# 00_dynaRoACH_MotorDriver_1_Chan.net
KiCad netlist of a schematic drawn in EAGLE
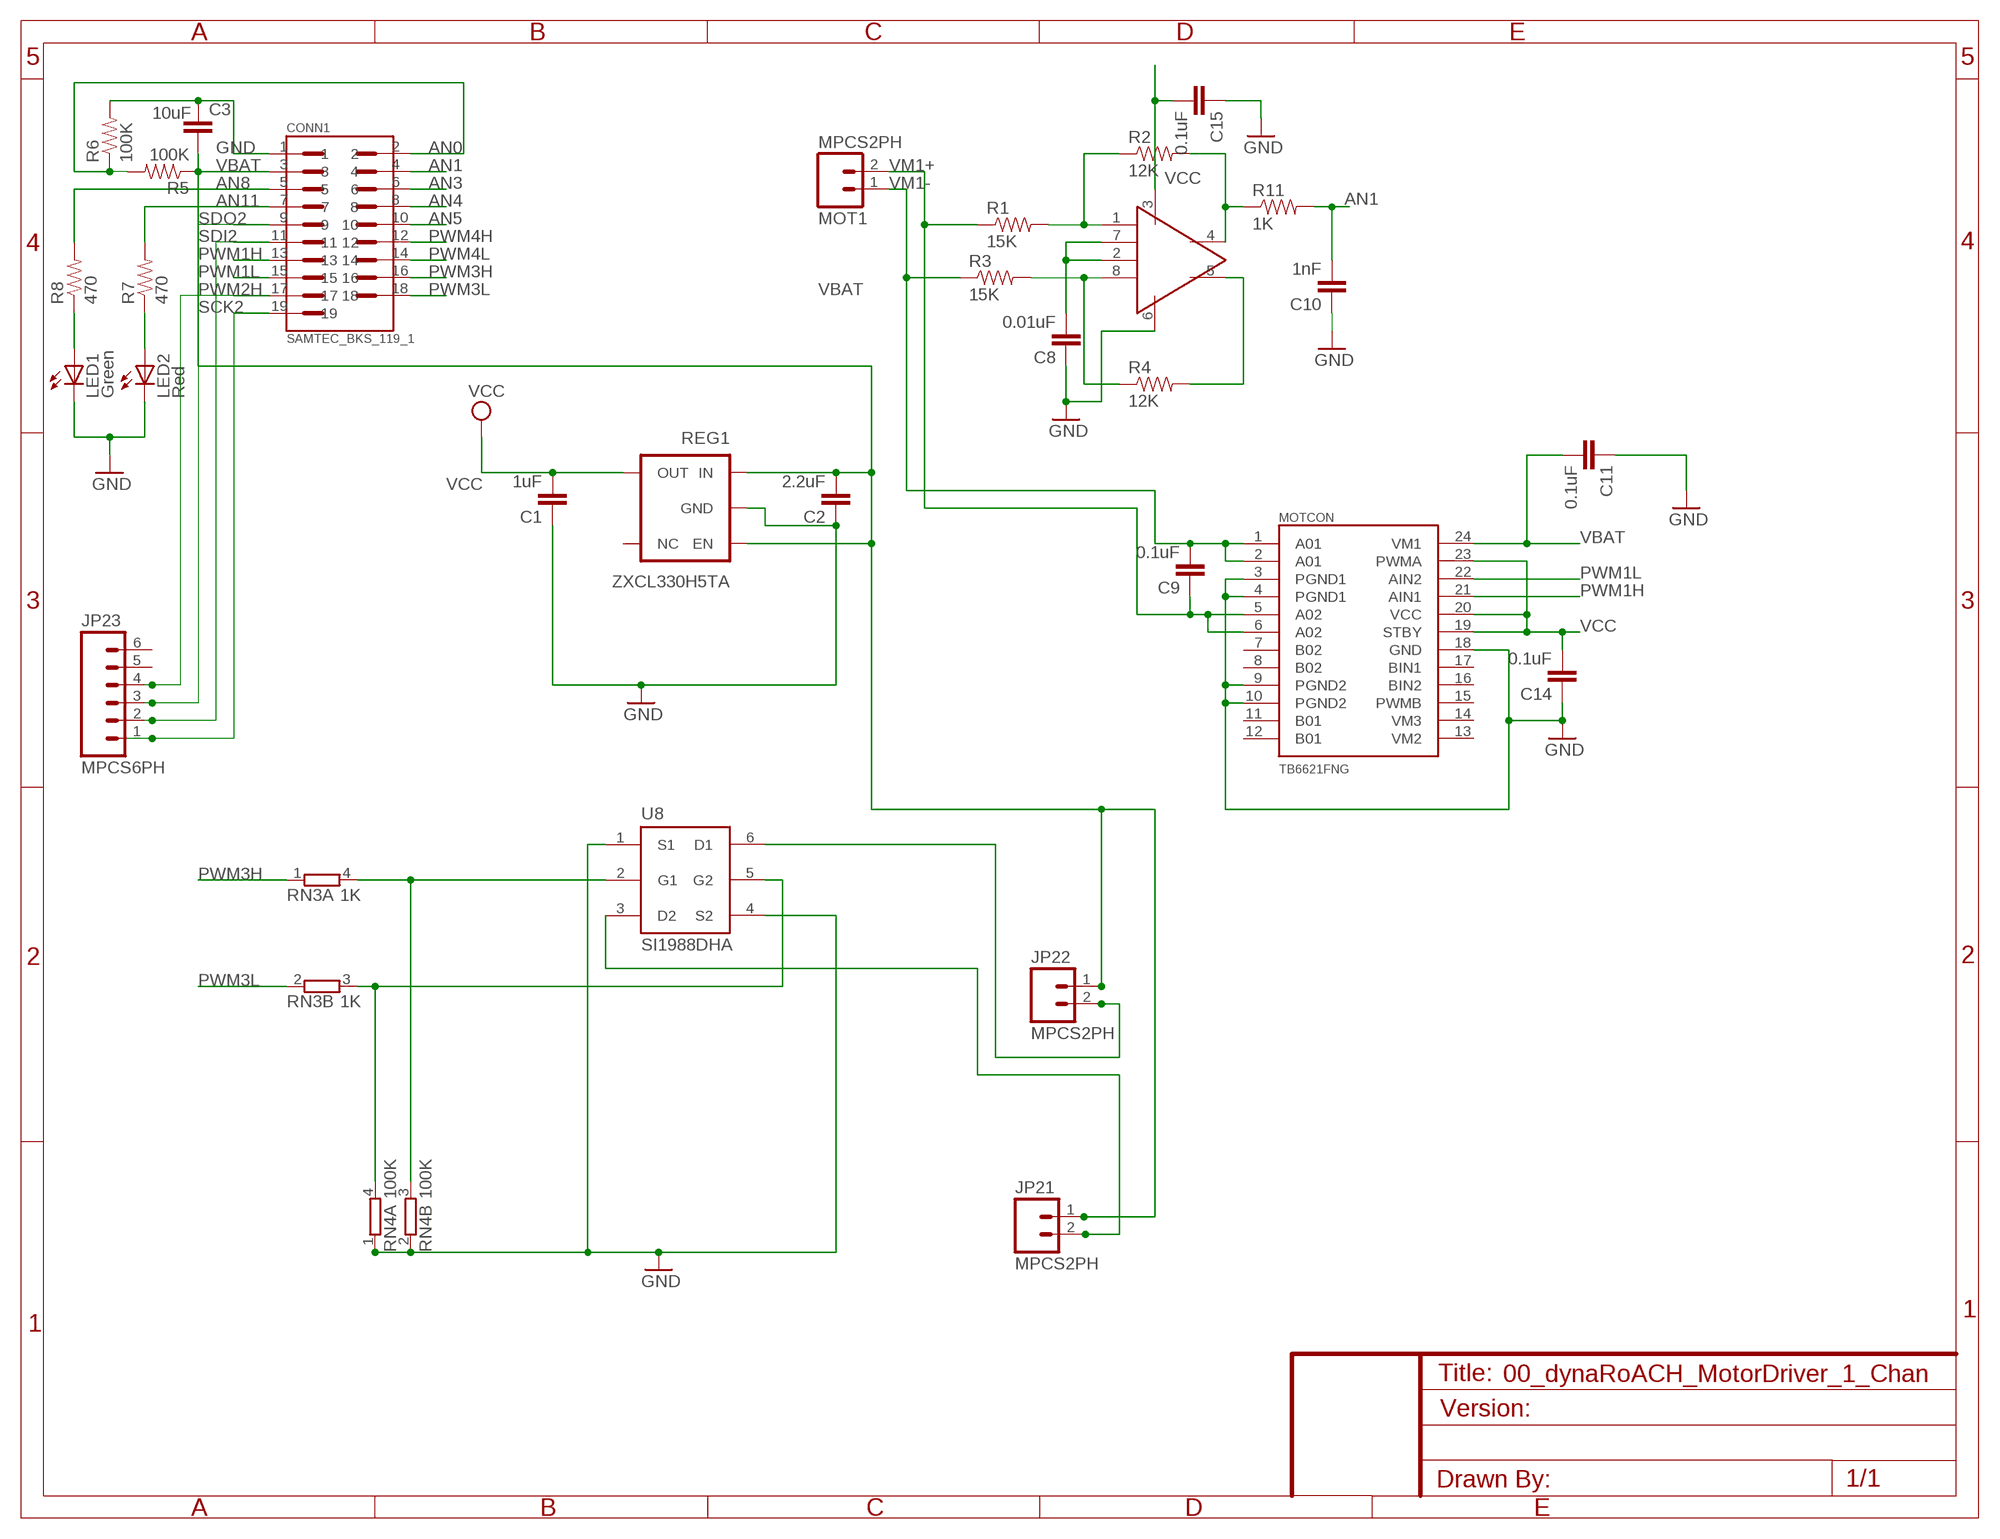
[diagram p0: schematic, sheet 1]

(export (version "E")
  (design (tool "Eeschema 10.0.6"))
  (components
    (comp (ref "C1")
      (value "1uF")
      (footprint "eagle-import:0402-CAP")
      (libsource (lib "eagle-import") (part "CAP0402-CAP"))
    )
    (comp (ref "C2")
      (value "2.2uF")
      (footprint "eagle-import:0402-CAP")
      (libsource (lib "eagle-import") (part "CAP0402-CAP"))
    )
    (comp (ref "C3")
      (value "10uF")
      (footprint "eagle-import:0603-CAP")
      (libsource (lib "eagle-import") (part "CAP0603-CAP"))
    )
    (comp (ref "C8")
      (value "0.01uF")
      (footprint "eagle-import:0402-CAP")
      (libsource (lib "eagle-import") (part "CAP0402-CAP"))
    )
    (comp (ref "C9")
      (value "0.1uF")
      (footprint "eagle-import:0402-CAP")
      (libsource (lib "eagle-import") (part "CAP0402-CAP"))
    )
    (comp (ref "C10")
      (value "1nF")
      (footprint "eagle-import:0402-CAP")
      (libsource (lib "eagle-import") (part "CAP0402-CAP"))
    )
    (comp (ref "C11")
      (value "0.1uF")
      (footprint "eagle-import:0402-CAP")
      (libsource (lib "eagle-import") (part "CAP0402-CAP"))
    )
    (comp (ref "C14")
      (value "0.1uF")
      (footprint "eagle-import:0402-CAP")
      (libsource (lib "eagle-import") (part "CAP0402-CAP"))
    )
    (comp (ref "C15")
      (value "0.1uF")
      (footprint "eagle-import:0402-CAP")
      (libsource (lib "eagle-import") (part "CAP0402-CAP"))
    )
    (comp (ref "CONN1")
      (value "SAMTEC_BKS_119_1")
      (footprint "eagle-import:SAMTEC_19P_1MM_SOCKET")
      (libsource (lib "eagle-import") (part "SAMTEC_BKS_119_1"))
    )
    (comp (ref "JP21")
      (value "MPCS2PH")
      (footprint "eagle-import:MOLEX-PICO_CLASP_S2P")
      (libsource (lib "eagle-import") (part "MPCS2PH"))
    )
    (comp (ref "JP22")
      (value "MPCS2PH")
      (footprint "eagle-import:MOLEX-PICO_CLASP_S2P")
      (libsource (lib "eagle-import") (part "MPCS2PH"))
    )
    (comp (ref "JP23")
      (value "MPCS6PH")
      (footprint "eagle-import:MOLEX-PICO_CLASP_S6P")
      (libsource (lib "eagle-import") (part "MPCS6PH"))
    )
    (comp (ref "LED1")
      (value "Green")
      (footprint "eagle-import:LED-0603")
      (libsource (lib "eagle-import") (part "LED0603"))
    )
    (comp (ref "LED2")
      (value "Red")
      (footprint "eagle-import:LED-0603")
      (libsource (lib "eagle-import") (part "LED0603"))
    )
    (comp (ref "MOT1")
      (value "MPCS2PH")
      (footprint "eagle-import:MOLEX-PICO_CLASP_S2P")
      (libsource (lib "eagle-import") (part "MPCS2PH"))
    )
    (comp (ref "MOTCON")
      (value "TB6621FNG")
      (footprint "eagle-import:SSOP24")
      (libsource (lib "eagle-import") (part "TB6621FNG"))
    )
    (comp (ref "R1")
      (value "15K")
      (footprint "eagle-import:0402-RES")
      (libsource (lib "eagle-import") (part "RESISTOR0402-RES"))
    )
    (comp (ref "R2")
      (value "12K")
      (footprint "eagle-import:0402-RES")
      (libsource (lib "eagle-import") (part "RESISTOR0402-RES"))
    )
    (comp (ref "R3")
      (value "15K")
      (footprint "eagle-import:0402-RES")
      (libsource (lib "eagle-import") (part "RESISTOR0402-RES"))
    )
    (comp (ref "R4")
      (value "12K")
      (footprint "eagle-import:0402-RES")
      (libsource (lib "eagle-import") (part "RESISTOR0402-RES"))
    )
    (comp (ref "R5")
      (value "100K")
      (footprint "eagle-import:0402-RES")
      (libsource (lib "eagle-import") (part "RESISTOR0402-RES"))
    )
    (comp (ref "R6")
      (value "100K")
      (footprint "eagle-import:0402-RES")
      (libsource (lib "eagle-import") (part "RESISTOR0402-RES"))
    )
    (comp (ref "R7")
      (value "470")
      (footprint "eagle-import:0402-RES")
      (libsource (lib "eagle-import") (part "RESISTOR0402-RES"))
    )
    (comp (ref "R8")
      (value "470")
      (footprint "eagle-import:0402-RES")
      (libsource (lib "eagle-import") (part "RESISTOR0402-RES"))
    )
    (comp (ref "R11")
      (value "1K")
      (footprint "eagle-import:0402-RES")
      (libsource (lib "eagle-import") (part "RESISTOR0402-RES"))
    )
    (comp (ref "REG1")
      (value "ZXCL330H5TA")
      (footprint "eagle-import:SC-70-5")
      (libsource (lib "eagle-import") (part "ZXCL330H5TA"))
    )
    (comp (ref "RN3")
      (value "1K")
      (footprint "eagle-import:EXB24V")
      (libsource (lib "eagle-import") (part "2R-NEXB24V"))
    )
    (comp (ref "RN4")
      (value "100K")
      (footprint "eagle-import:EXB24V")
      (libsource (lib "eagle-import") (part "2R-NEXB24V"))
    )
    (comp (ref "U$1")
      (value "LTC1992")
      (footprint "eagle-import:8-PIN_MSOP")
      (libsource (lib "eagle-import") (part "LTC1992"))
    )
    (comp (ref "U8")
      (value "SI1988DHA")
      (footprint "eagle-import:SC-70-6")
      (libsource (lib "eagle-import") (part "SI1988DHA"))
    )
  )
  (nets
    (net (code "1") (name "/AN0") (class "Default")
      (node (ref "CONN1") (pin "2") (pinfunction "2_2") (pintype "passive"))
      (node (ref "R5") (pin "2") (pinfunction "2_2") (pintype "passive"))
      (node (ref "R6") (pin "1") (pinfunction "1_1") (pintype "passive"))
    )
    (net (code "2") (name "/AN1") (class "Default")
      (node (ref "C10") (pin "2") (pinfunction "2_2") (pintype "passive"))
      (node (ref "CONN1") (pin "4") (pinfunction "4_4") (pintype "passive"))
      (node (ref "R11") (pin "2") (pinfunction "2_2") (pintype "passive"))
    )
    (net (code "3") (name "/AN3") (class "Default")
      (node (ref "CONN1") (pin "6") (pinfunction "6_6") (pintype "passive"))
    )
    (net (code "4") (name "/AN4") (class "Default")
      (node (ref "CONN1") (pin "8") (pinfunction "8_8") (pintype "passive"))
    )
    (net (code "5") (name "/AN5") (class "Default")
      (node (ref "CONN1") (pin "10") (pinfunction "10_10") (pintype "passive"))
    )
    (net (code "6") (name "/AN8") (class "Default")
      (node (ref "CONN1") (pin "5") (pinfunction "5_5") (pintype "passive"))
      (node (ref "R8") (pin "2") (pinfunction "2_2") (pintype "passive"))
    )
    (net (code "7") (name "/AN11") (class "Default")
      (node (ref "CONN1") (pin "7") (pinfunction "7_7") (pintype "passive"))
      (node (ref "R7") (pin "2") (pinfunction "2_2") (pintype "passive"))
    )
    (net (code "8") (name "/PWM1H") (class "Default")
      (node (ref "CONN1") (pin "13") (pinfunction "13_13") (pintype "passive"))
      (node (ref "MOTCON") (pin "21") (pinfunction "AIN1_21") (pintype "bidirectional"))
    )
    (net (code "9") (name "/PWM1L") (class "Default")
      (node (ref "CONN1") (pin "15") (pinfunction "15_15") (pintype "passive"))
      (node (ref "MOTCON") (pin "22") (pinfunction "AIN2_22") (pintype "bidirectional"))
    )
    (net (code "10") (name "/PWM2H") (class "Default")
      (node (ref "CONN1") (pin "17") (pinfunction "17_17") (pintype "passive"))
      (node (ref "JP23") (pin "4") (pinfunction "4_4") (pintype "passive"))
    )
    (net (code "11") (name "/PWM3H") (class "Default")
      (node (ref "CONN1") (pin "16") (pinfunction "16_16") (pintype "passive"))
      (node (ref "RN3") (pin "1") (pinfunction "1_1") (pintype "passive"))
    )
    (net (code "12") (name "/PWM3L") (class "Default")
      (node (ref "CONN1") (pin "18") (pinfunction "18_18") (pintype "passive"))
      (node (ref "RN3") (pin "2") (pinfunction "1_2") (pintype "passive"))
    )
    (net (code "13") (name "/PWM4H") (class "Default")
      (node (ref "CONN1") (pin "12") (pinfunction "12_12") (pintype "passive"))
    )
    (net (code "14") (name "/PWM4L") (class "Default")
      (node (ref "CONN1") (pin "14") (pinfunction "14_14") (pintype "passive"))
    )
    (net (code "15") (name "/SCK2") (class "Default")
      (node (ref "CONN1") (pin "19") (pinfunction "19_19") (pintype "passive"))
      (node (ref "JP23") (pin "1") (pinfunction "1_1") (pintype "passive"))
    )
    (net (code "16") (name "/SDI2") (class "Default")
      (node (ref "CONN1") (pin "11") (pinfunction "11_11") (pintype "passive"))
      (node (ref "JP23") (pin "2") (pinfunction "2_2") (pintype "passive"))
    )
    (net (code "17") (name "/SDO2") (class "Default")
      (node (ref "CONN1") (pin "9") (pinfunction "9_9") (pintype "passive"))
      (node (ref "JP23") (pin "3") (pinfunction "3_3") (pintype "passive"))
    )
    (net (code "18") (name "/VBAT") (class "Default")
      (node (ref "C11") (pin "2") (pinfunction "2_2") (pintype "passive"))
      (node (ref "C2") (pin "2") (pinfunction "2_2") (pintype "passive"))
      (node (ref "C3") (pin "2") (pinfunction "2_2") (pintype "passive"))
      (node (ref "CONN1") (pin "3") (pinfunction "3_3") (pintype "passive"))
      (node (ref "JP21") (pin "1") (pinfunction "1_1") (pintype "passive"))
      (node (ref "JP22") (pin "1") (pinfunction "1_1") (pintype "passive"))
      (node (ref "MOTCON") (pin "24") (pinfunction "VM1_24") (pintype "bidirectional"))
      (node (ref "R5") (pin "1") (pinfunction "1_1") (pintype "passive"))
      (node (ref "REG1") (pin "1") (pinfunction "IN_1") (pintype "input"))
      (node (ref "REG1") (pin "3") (pinfunction "EN_3") (pintype "input"))
    )
    (net (code "19") (name "/VM1+") (class "Default")
      (node (ref "C9") (pin "1") (pinfunction "1_1") (pintype "passive"))
      (node (ref "MOT1") (pin "2") (pinfunction "2_2") (pintype "passive"))
      (node (ref "MOTCON") (pin "5") (pinfunction "A02_5") (pintype "bidirectional"))
      (node (ref "MOTCON") (pin "6") (pinfunction "A02_6") (pintype "bidirectional"))
      (node (ref "R1") (pin "1") (pinfunction "1_1") (pintype "passive"))
    )
    (net (code "20") (name "/VM1-") (class "Default")
      (node (ref "C9") (pin "2") (pinfunction "2_2") (pintype "passive"))
      (node (ref "MOT1") (pin "1") (pinfunction "1_1") (pintype "passive"))
      (node (ref "MOTCON") (pin "1") (pinfunction "A01_1") (pintype "bidirectional"))
      (node (ref "MOTCON") (pin "2") (pinfunction "A01_2") (pintype "bidirectional"))
      (node (ref "R3") (pin "1") (pinfunction "1_1") (pintype "passive"))
    )
    (net (code "21") (name "GND") (class "Default")
      (node (ref "C1") (pin "1") (pinfunction "1_1") (pintype "passive"))
      (node (ref "C10") (pin "1") (pinfunction "1_1") (pintype "passive"))
      (node (ref "C11") (pin "1") (pinfunction "1_1") (pintype "passive"))
      (node (ref "C14") (pin "1") (pinfunction "1_1") (pintype "passive"))
      (node (ref "C15") (pin "1") (pinfunction "1_1") (pintype "passive"))
      (node (ref "C2") (pin "1") (pinfunction "1_1") (pintype "passive"))
      (node (ref "C3") (pin "1") (pinfunction "1_1") (pintype "passive"))
      (node (ref "C8") (pin "1") (pinfunction "1_1") (pintype "passive"))
      (node (ref "CONN1") (pin "1") (pinfunction "1_1") (pintype "passive"))
      (node (ref "LED1") (pin "C") (pinfunction "C_C") (pintype "passive"))
      (node (ref "LED2") (pin "C") (pinfunction "C_C") (pintype "passive"))
      (node (ref "MOTCON") (pin "10") (pinfunction "PGND2_10") (pintype "bidirectional"))
      (node (ref "MOTCON") (pin "18") (pinfunction "GND_18") (pintype "bidirectional"))
      (node (ref "MOTCON") (pin "3") (pinfunction "PGND1_3") (pintype "bidirectional"))
      (node (ref "MOTCON") (pin "4") (pinfunction "PGND1_4") (pintype "bidirectional"))
      (node (ref "MOTCON") (pin "9") (pinfunction "PGND2_9") (pintype "bidirectional"))
      (node (ref "R6") (pin "2") (pinfunction "2_2") (pintype "passive"))
      (node (ref "REG1") (pin "2") (pinfunction "GND_2") (pintype "input"))
      (node (ref "RN4") (pin "1") (pinfunction "1_1") (pintype "passive"))
      (node (ref "RN4") (pin "2") (pinfunction "1_2") (pintype "passive"))
      (node (ref "U$1") (pin "6") (pinfunction "GND_6") (pintype "bidirectional"))
      (node (ref "U8") (pin "1") (pinfunction "S1_1") (pintype "bidirectional"))
      (node (ref "U8") (pin "4") (pinfunction "S2_4") (pintype "bidirectional"))
    )
    (net (code "22") (name "Net-(LED1-PadA)") (class "Default")
      (node (ref "LED1") (pin "A") (pinfunction "A_A") (pintype "passive"))
      (node (ref "R8") (pin "1") (pinfunction "1_1") (pintype "passive"))
    )
    (net (code "23") (name "Net-(LED2-PadA)") (class "Default")
      (node (ref "LED2") (pin "A") (pinfunction "A_A") (pintype "passive"))
      (node (ref "R7") (pin "1") (pinfunction "1_1") (pintype "passive"))
    )
    (net (code "24") (name "Net-(RN3A-2)") (class "Default")
      (node (ref "RN3") (pin "4") (pinfunction "2_4") (pintype "passive"))
      (node (ref "RN4") (pin "3") (pinfunction "2_3") (pintype "passive"))
      (node (ref "U8") (pin "2") (pinfunction "G1_2") (pintype "bidirectional"))
    )
    (net (code "25") (name "Net-(RN3B-2)") (class "Default")
      (node (ref "RN3") (pin "3") (pinfunction "2_3") (pintype "passive"))
      (node (ref "RN4") (pin "4") (pinfunction "2_4") (pintype "passive"))
      (node (ref "U8") (pin "5") (pinfunction "G2_5") (pintype "bidirectional"))
    )
    (net (code "26") (name "Net-(U$1-+)") (class "Default")
      (node (ref "R3") (pin "2") (pinfunction "2_2") (pintype "passive"))
      (node (ref "R4") (pin "1") (pinfunction "1_1") (pintype "passive"))
      (node (ref "U$1") (pin "8") (pinfunction "+_8") (pintype "bidirectional"))
    )
    (net (code "27") (name "Net-(U$1--)") (class "Default")
      (node (ref "R1") (pin "2") (pinfunction "2_2") (pintype "passive"))
      (node (ref "R2") (pin "1") (pinfunction "1_1") (pintype "passive"))
      (node (ref "U$1") (pin "1") (pinfunction "-_1") (pintype "bidirectional"))
    )
    (net (code "28") (name "Net-(U$1-OUT+)") (class "Default")
      (node (ref "R11") (pin "1") (pinfunction "1_1") (pintype "passive"))
      (node (ref "R2") (pin "2") (pinfunction "2_2") (pintype "passive"))
      (node (ref "U$1") (pin "4") (pinfunction "OUT+_4") (pintype "bidirectional"))
    )
    (net (code "29") (name "Net-(U$1-OUT-)") (class "Default")
      (node (ref "R4") (pin "2") (pinfunction "2_2") (pintype "passive"))
      (node (ref "U$1") (pin "5") (pinfunction "OUT-_5") (pintype "bidirectional"))
    )
    (net (code "30") (name "Net-(U$1-V_MID)") (class "Default")
      (node (ref "C8") (pin "2") (pinfunction "2_2") (pintype "passive"))
      (node (ref "U$1") (pin "2") (pinfunction "V_OCM_2") (pintype "bidirectional"))
      (node (ref "U$1") (pin "7") (pinfunction "V_MID_7") (pintype "bidirectional"))
    )
    (net (code "31") (name "Net-(U8-D1)") (class "Default")
      (node (ref "JP22") (pin "2") (pinfunction "2_2") (pintype "passive"))
      (node (ref "U8") (pin "6") (pinfunction "D1_6") (pintype "bidirectional"))
    )
    (net (code "32") (name "Net-(U8-D2)") (class "Default")
      (node (ref "JP21") (pin "2") (pinfunction "2_2") (pintype "passive"))
      (node (ref "U8") (pin "3") (pinfunction "D2_3") (pintype "bidirectional"))
    )
    (net (code "33") (name "VCC") (class "Default")
      (node (ref "C1") (pin "2") (pinfunction "2_2") (pintype "passive"))
      (node (ref "C14") (pin "2") (pinfunction "2_2") (pintype "passive"))
      (node (ref "C15") (pin "2") (pinfunction "2_2") (pintype "passive"))
      (node (ref "MOTCON") (pin "19") (pinfunction "STBY_19") (pintype "bidirectional"))
      (node (ref "MOTCON") (pin "20") (pinfunction "VCC_20") (pintype "bidirectional"))
      (node (ref "MOTCON") (pin "23") (pinfunction "PWMA_23") (pintype "bidirectional"))
      (node (ref "REG1") (pin "5") (pinfunction "OUT_5") (pintype "passive"))
      (node (ref "U$1") (pin "3") (pinfunction "VDD_3") (pintype "bidirectional"))
    )
    (net (code "34") (name "unconnected-(JP23-Pad5)") (class "Default")
      (node (ref "JP23") (pin "5") (pinfunction "5_5") (pintype "passive"))
    )
    (net (code "35") (name "unconnected-(JP23-Pad6)") (class "Default")
      (node (ref "JP23") (pin "6") (pinfunction "6_6") (pintype "passive"))
    )
    (net (code "36") (name "unconnected-(MOTCON-B01-Pad11)") (class "Default")
      (node (ref "MOTCON") (pin "11") (pinfunction "B01_11") (pintype "bidirectional"))
    )
    (net (code "37") (name "unconnected-(MOTCON-B01-Pad12)") (class "Default")
      (node (ref "MOTCON") (pin "12") (pinfunction "B01_12") (pintype "bidirectional"))
    )
    (net (code "38") (name "unconnected-(MOTCON-B02-Pad7)") (class "Default")
      (node (ref "MOTCON") (pin "7") (pinfunction "B02_7") (pintype "bidirectional"))
    )
    (net (code "39") (name "unconnected-(MOTCON-B02-Pad8)") (class "Default")
      (node (ref "MOTCON") (pin "8") (pinfunction "B02_8") (pintype "bidirectional"))
    )
    (net (code "40") (name "unconnected-(MOTCON-BIN1-Pad17)") (class "Default")
      (node (ref "MOTCON") (pin "17") (pinfunction "BIN1_17") (pintype "bidirectional"))
    )
    (net (code "41") (name "unconnected-(MOTCON-BIN2-Pad16)") (class "Default")
      (node (ref "MOTCON") (pin "16") (pinfunction "BIN2_16") (pintype "bidirectional"))
    )
    (net (code "42") (name "unconnected-(MOTCON-PWMB-Pad15)") (class "Default")
      (node (ref "MOTCON") (pin "15") (pinfunction "PWMB_15") (pintype "bidirectional"))
    )
    (net (code "43") (name "unconnected-(MOTCON-VM2-Pad13)") (class "Default")
      (node (ref "MOTCON") (pin "13") (pinfunction "VM2_13") (pintype "bidirectional"))
    )
    (net (code "44") (name "unconnected-(MOTCON-VM3-Pad14)") (class "Default")
      (node (ref "MOTCON") (pin "14") (pinfunction "VM3_14") (pintype "bidirectional"))
    )
    (net (code "45") (name "unconnected-(REG1-NC-Pad4)") (class "Default")
      (node (ref "REG1") (pin "4") (pinfunction "NC_4") (pintype "input"))
    )
  )
)
